# PwrSupply.net
KiCad netlist of a schematic drawn in Altium Designer
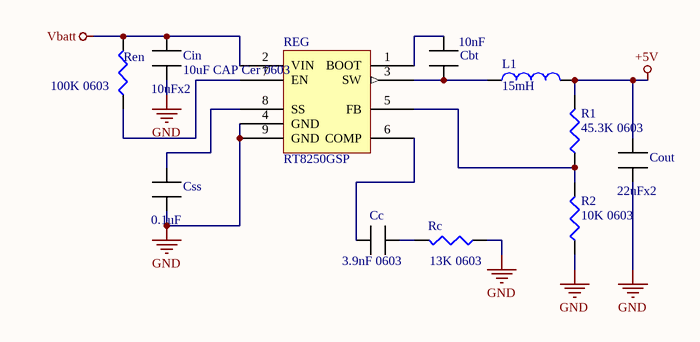
[diagram p0: PwrSupply.SchDoc]

(export (version "E")
  (design (tool "Eeschema 10.0.6"))
  (components
    (comp (ref "Cbt")
      (value "10nF")
      (footprint "Miscellaneous Devices:J1-0603")
      (description "Capacitor")
      (fields (field (name "Comment") "10nF 0603"))
      (libsource (lib "RpiPaw1_SchLib") (part "CAP"))
    )
    (comp (ref "Cc")
      (value "3.9nF 0603")
      (footprint "Miscellaneous Devices:J1-0603")
      (description "Capacitor")
      (libsource (lib "RpiPaw1_SchLib") (part "CAP"))
    )
    (comp (ref "Cin")
      (value "10uF CAP Cer 0603")
      (footprint "Miscellaneous Devices:J1-0603")
      (description "Capacitor")
      (fields (field (name "ALTIUM_VALUE") "10uFx2"))
      (libsource (lib "RpiPaw1_SchLib") (part "CAP"))
    )
    (comp (ref "Cout")
      (value "22uFx2")
      (footprint "Miscellaneous Devices:C0805")
      (description "Capacitor")
      (fields (field (name "Comment") "22uF CAP CER 0805"))
      (libsource (lib "RpiPaw1_SchLib") (part "CAP"))
    )
    (comp (ref "Css")
      (value "0.1uF")
      (footprint "Miscellaneous Devices:J1-0603")
      (description "Capacitor")
      (fields (field (name "Comment") "0.1uF CAP CER 0603"))
      (libsource (lib "RpiPaw1_SchLib") (part "CAP"))
    )
    (comp (ref "L1")
      (value "15mH")
      (footprint "Inductor_Paw")
      (description "Inductor")
      (fields (field (name "PUBLISHER") "Altium Limited"))
      (libsource (lib "Miscellaneous Devices") (part "Inductor"))
    )
    (comp (ref "R1")
      (value "45.3K 0603")
      (footprint "J1-0603")
      (description "Resistor")
      (fields (field (name "PUBLISHER") "Altium Limited"))
      (libsource (lib "Miscellaneous Devices") (part "Res3"))
    )
    (comp (ref "R2")
      (value "10K 0603")
      (footprint "J1-0603")
      (description "Resistor")
      (fields (field (name "PUBLISHER") "Altium Limited"))
      (libsource (lib "Miscellaneous Devices") (part "Res3"))
    )
    (comp (ref "Rc")
      (value "13K 0603")
      (footprint "J1-0603")
      (description "Resistor")
      (fields (field (name "PUBLISHER") "Altium Limited"))
      (libsource (lib "Miscellaneous Devices") (part "Res3"))
    )
    (comp (ref "REG")
      (value "RT8250GSP")
      (footprint "RF Micro Devices Footprints:SOP-8-C_N")
      (description "3A 5V Buck Regulator")
      (libsource (lib "RpiPaw1_SchLib") (part "RT8250GSP"))
    )
    (comp (ref "Ren")
      (value "100K 0603")
      (footprint "J1-0603")
      (description "Resistor")
      (fields (field (name "PUBLISHER") "Altium Limited"))
      (libsource (lib "Miscellaneous Devices") (part "Res3"))
    )
  )
  (nets
    (net (code "1") (name "+5V") (class "Default")
      (node (ref "Cout") (pin "2") (pinfunction "P2_2") (pintype "passive"))
      (node (ref "L1") (pin "2") (pinfunction "2_2") (pintype "passive"))
      (node (ref "R1") (pin "2") (pinfunction "2_2") (pintype "passive"))
    )
    (net (code "2") (name "GND") (class "Default")
      (node (ref "Cin") (pin "1") (pinfunction "P1_1") (pintype "passive"))
      (node (ref "Cout") (pin "1") (pinfunction "P1_1") (pintype "passive"))
      (node (ref "Css") (pin "1") (pinfunction "P1_1") (pintype "passive"))
      (node (ref "R2") (pin "1") (pinfunction "1_1") (pintype "passive"))
      (node (ref "REG") (pin "4") (pinfunction "GND_4") (pintype "passive"))
      (node (ref "REG") (pin "9") (pinfunction "GND_9") (pintype "passive"))
      (node (ref "Rc") (pin "1") (pinfunction "1_1") (pintype "passive"))
    )
    (net (code "3") (name "Net-(Cbt-P1)") (class "Default")
      (node (ref "Cbt") (pin "1") (pinfunction "P1_1") (pintype "passive"))
      (node (ref "L1") (pin "1") (pinfunction "1_1") (pintype "passive"))
      (node (ref "REG") (pin "3") (pinfunction "SW_3") (pintype "output"))
    )
    (net (code "4") (name "Net-(Cbt-P2)") (class "Default")
      (node (ref "Cbt") (pin "2") (pinfunction "P2_2") (pintype "passive"))
      (node (ref "REG") (pin "1") (pinfunction "BOOT_1") (pintype "passive"))
    )
    (net (code "5") (name "Net-(Cc-P1)") (class "Default")
      (node (ref "Cc") (pin "1") (pinfunction "P1_1") (pintype "passive"))
      (node (ref "REG") (pin "6") (pinfunction "COMP_6") (pintype "passive"))
    )
    (net (code "6") (name "Net-(Cc-P2)") (class "Default")
      (node (ref "Cc") (pin "2") (pinfunction "P2_2") (pintype "passive"))
      (node (ref "Rc") (pin "2") (pinfunction "2_2") (pintype "passive"))
    )
    (net (code "7") (name "Net-(Css-P2)") (class "Default")
      (node (ref "Css") (pin "2") (pinfunction "P2_2") (pintype "passive"))
      (node (ref "REG") (pin "8") (pinfunction "SS_8") (pintype "passive"))
    )
    (net (code "8") (name "Net-(REG-EN)") (class "Default")
      (node (ref "REG") (pin "7") (pinfunction "EN_7") (pintype "passive"))
      (node (ref "Ren") (pin "1") (pinfunction "1_1") (pintype "passive"))
    )
    (net (code "9") (name "Net-(REG-FB)") (class "Default")
      (node (ref "R1") (pin "1") (pinfunction "1_1") (pintype "passive"))
      (node (ref "R2") (pin "2") (pinfunction "2_2") (pintype "passive"))
      (node (ref "REG") (pin "5") (pinfunction "FB_5") (pintype "passive"))
    )
    (net (code "10") (name "Vbatt") (class "Default")
      (node (ref "Cin") (pin "2") (pinfunction "P2_2") (pintype "passive"))
      (node (ref "REG") (pin "2") (pinfunction "VIN_2") (pintype "power_in"))
      (node (ref "Ren") (pin "2") (pinfunction "2_2") (pintype "passive"))
    )
  )
)
